# working.net
KiCad netlist of a schematic drawn in EAGLE
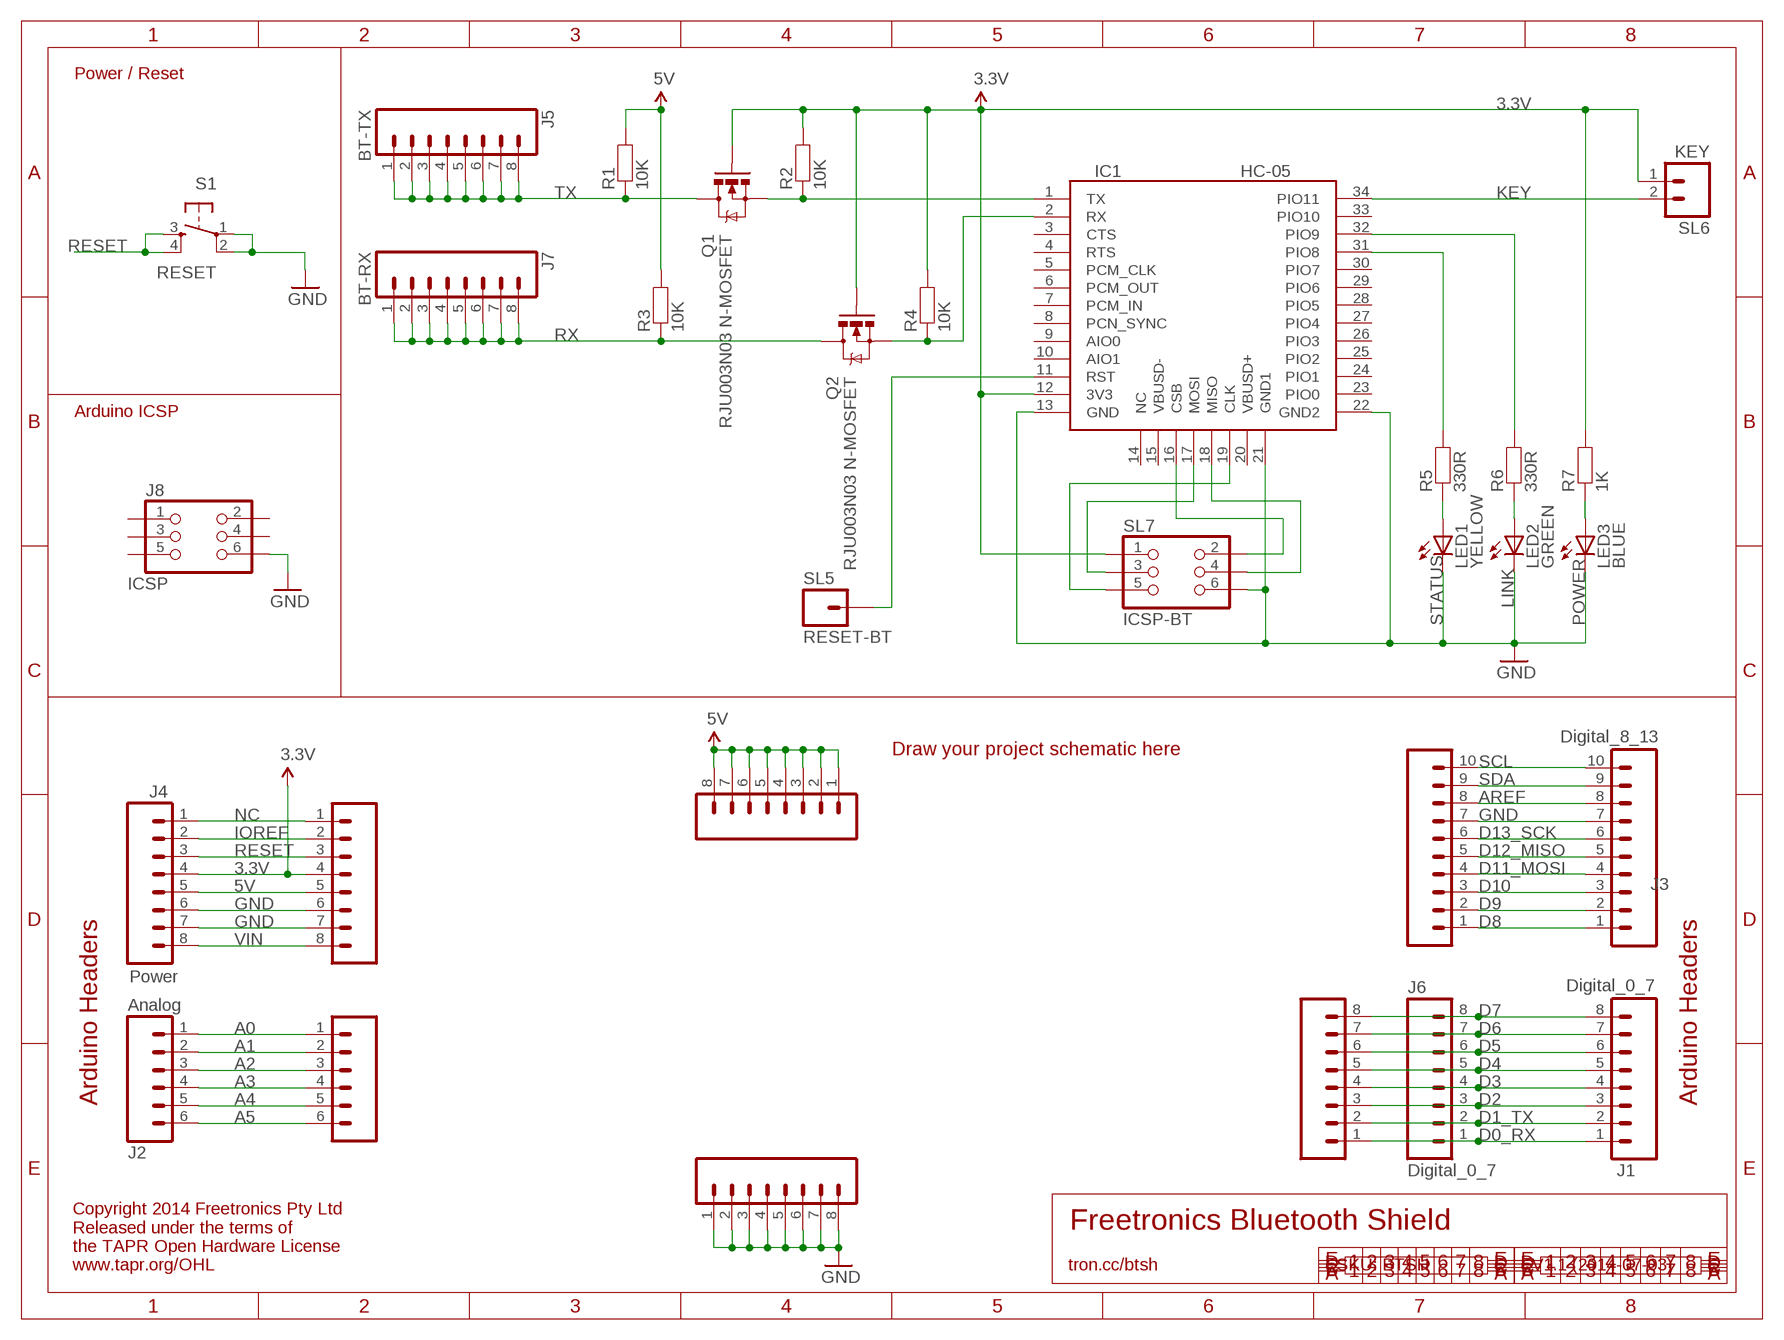
[diagram p0: schematic, sheet 1]

(export (version "E")
  (design (tool "Eeschema 10.0.6"))
  (components
    (comp (ref "IC1")
      (value "HC-05")
      (footprint "eagle-import:BLUETOOTH_SMD")
      (libsource (lib "eagle-import") (part "HC_05"))
    )
    (comp (ref "J1")
      (value "Digital_0_7")
      (footprint "eagle-import:1X08")
      (libsource (lib "eagle-import") (part "M08"))
    )
    (comp (ref "J2")
      (value "Analog")
      (footprint "eagle-import:1X06")
      (libsource (lib "eagle-import") (part "M06SIP"))
    )
    (comp (ref "J3")
      (value "Digital_8_13")
      (footprint "eagle-import:1X10")
      (libsource (lib "eagle-import") (part "M100.1"))
    )
    (comp (ref "J4")
      (value "Power")
      (footprint "eagle-import:1X08")
      (libsource (lib "eagle-import") (part "M08"))
    )
    (comp (ref "J5")
      (value "BT-TX")
      (footprint "eagle-import:1X08")
      (libsource (lib "eagle-import") (part "freetronics-original_M08"))
    )
    (comp (ref "J6")
      (value "Digital_0_7")
      (footprint "eagle-import:1X08")
      (libsource (lib "eagle-import") (part "freetronics-original_M08"))
    )
    (comp (ref "J7")
      (value "BT-RX")
      (footprint "eagle-import:1X08")
      (libsource (lib "eagle-import") (part "freetronics-original_M08"))
    )
    (comp (ref "J8")
      (value "ICSP")
      (footprint "eagle-import:2X03PTH")
      (libsource (lib "eagle-import") (part "ICSPPTH"))
    )
    (comp (ref "LED1")
      (value "YELLOW")
      (footprint "eagle-import:LED-0603")
      (libsource (lib "eagle-import") (part "LED0603"))
    )
    (comp (ref "LED2")
      (value "GREEN")
      (footprint "eagle-import:LED-0603")
      (libsource (lib "eagle-import") (part "LED0603"))
    )
    (comp (ref "LED3")
      (value "BLUE")
      (footprint "eagle-import:LED-0603")
      (libsource (lib "eagle-import") (part "LED0603"))
    )
    (comp (ref "Q1")
      (value "RJU003N03 N-MOSFET")
      (footprint "eagle-import:SOT32-3")
      (libsource (lib "eagle-import") (part "MOSFET-NSOT-323"))
    )
    (comp (ref "Q2")
      (value "RJU003N03 N-MOSFET")
      (footprint "eagle-import:SOT32-3")
      (libsource (lib "eagle-import") (part "MOSFET-NSOT-323"))
    )
    (comp (ref "R1")
      (value "10K")
      (footprint "eagle-import:0603")
      (libsource (lib "eagle-import") (part "RESISTOR0603"))
    )
    (comp (ref "R2")
      (value "10K")
      (footprint "eagle-import:0603")
      (libsource (lib "eagle-import") (part "RESISTOR0603"))
    )
    (comp (ref "R3")
      (value "10K")
      (footprint "eagle-import:0603")
      (libsource (lib "eagle-import") (part "RESISTOR0603"))
    )
    (comp (ref "R4")
      (value "10K")
      (footprint "eagle-import:0603")
      (libsource (lib "eagle-import") (part "RESISTOR0603"))
    )
    (comp (ref "R5")
      (value "330R")
      (footprint "eagle-import:0603")
      (libsource (lib "eagle-import") (part "RESISTOR0603"))
    )
    (comp (ref "R6")
      (value "330R")
      (footprint "eagle-import:0603")
      (libsource (lib "eagle-import") (part "RESISTOR0603"))
    )
    (comp (ref "R7")
      (value "1K")
      (footprint "eagle-import:0603")
      (libsource (lib "eagle-import") (part "RESISTOR0603"))
    )
    (comp (ref "S1")
      (value "RESET")
      (footprint "eagle-import:TACTILE_SWITCH_SMD")
      (libsource (lib "eagle-import") (part "TAC_SWITCHSMD"))
    )
    (comp (ref "SL1")
      (value "Digital_0_7")
      (footprint "eagle-import:1X08")
      (libsource (lib "eagle-import") (part "M08"))
    )
    (comp (ref "SL2")
      (value "Analog")
      (footprint "eagle-import:1X06")
      (libsource (lib "eagle-import") (part "M06SIP"))
    )
    (comp (ref "SL3")
      (value "Digital_8_13")
      (footprint "eagle-import:1X10")
      (libsource (lib "eagle-import") (part "M100.1"))
    )
    (comp (ref "SL4")
      (value "Power")
      (footprint "eagle-import:1X08")
      (libsource (lib "eagle-import") (part "M08"))
    )
    (comp (ref "SL5")
      (value "RESET-BT")
      (footprint "eagle-import:1X01")
      (libsource (lib "eagle-import") (part "M01PTH"))
    )
    (comp (ref "SL6")
      (value "KEY")
      (footprint "eagle-import:1X02")
      (libsource (lib "eagle-import") (part "M02PTH"))
    )
    (comp (ref "SL7")
      (value "ICSP-BT")
      (footprint "eagle-import:2X03PTH")
      (libsource (lib "eagle-import") (part "ICSPPTH"))
    )
    (comp (ref "SL8")
      (value "5V")
      (footprint "eagle-import:1X08")
      (libsource (lib "eagle-import") (part "M08"))
    )
    (comp (ref "SL9")
      (value "GND")
      (footprint "eagle-import:1X08")
      (libsource (lib "eagle-import") (part "M08"))
    )
  )
  (nets
    (net (code "1") (name "/A0") (class "Default")
      (node (ref "J2") (pin "1") (pinfunction "1_1") (pintype "passive"))
      (node (ref "SL2") (pin "1") (pinfunction "1_1") (pintype "passive"))
    )
    (net (code "2") (name "/A1") (class "Default")
      (node (ref "J2") (pin "2") (pinfunction "2_2") (pintype "passive"))
      (node (ref "SL2") (pin "2") (pinfunction "2_2") (pintype "passive"))
    )
    (net (code "3") (name "/A2") (class "Default")
      (node (ref "J2") (pin "3") (pinfunction "3_3") (pintype "passive"))
      (node (ref "SL2") (pin "3") (pinfunction "3_3") (pintype "passive"))
    )
    (net (code "4") (name "/A3") (class "Default")
      (node (ref "J2") (pin "4") (pinfunction "4_4") (pintype "passive"))
      (node (ref "SL2") (pin "4") (pinfunction "4_4") (pintype "passive"))
    )
    (net (code "5") (name "/A4") (class "Default")
      (node (ref "J2") (pin "5") (pinfunction "5_5") (pintype "passive"))
      (node (ref "SL2") (pin "5") (pinfunction "5_5") (pintype "passive"))
    )
    (net (code "6") (name "/A5") (class "Default")
      (node (ref "J2") (pin "6") (pinfunction "6_6") (pintype "passive"))
      (node (ref "SL2") (pin "6") (pinfunction "6_6") (pintype "passive"))
    )
    (net (code "7") (name "/AREF") (class "Default")
      (node (ref "J3") (pin "8") (pinfunction "8_8") (pintype "passive"))
      (node (ref "SL3") (pin "8") (pinfunction "8_8") (pintype "passive"))
    )
    (net (code "8") (name "/D0_RX") (class "Default")
      (node (ref "J1") (pin "1") (pinfunction "1_1") (pintype "passive"))
      (node (ref "J6") (pin "1") (pinfunction "1_1") (pintype "passive"))
      (node (ref "SL1") (pin "1") (pinfunction "1_1") (pintype "passive"))
    )
    (net (code "9") (name "/D1_TX") (class "Default")
      (node (ref "J1") (pin "2") (pinfunction "2_2") (pintype "passive"))
      (node (ref "J6") (pin "2") (pinfunction "2_2") (pintype "passive"))
      (node (ref "SL1") (pin "2") (pinfunction "2_2") (pintype "passive"))
    )
    (net (code "10") (name "/D2") (class "Default")
      (node (ref "J1") (pin "3") (pinfunction "3_3") (pintype "passive"))
      (node (ref "J6") (pin "3") (pinfunction "3_3") (pintype "passive"))
      (node (ref "SL1") (pin "3") (pinfunction "3_3") (pintype "passive"))
    )
    (net (code "11") (name "/D3") (class "Default")
      (node (ref "J1") (pin "4") (pinfunction "4_4") (pintype "passive"))
      (node (ref "J6") (pin "4") (pinfunction "4_4") (pintype "passive"))
      (node (ref "SL1") (pin "4") (pinfunction "4_4") (pintype "passive"))
    )
    (net (code "12") (name "/D4") (class "Default")
      (node (ref "J1") (pin "5") (pinfunction "5_5") (pintype "passive"))
      (node (ref "J6") (pin "5") (pinfunction "5_5") (pintype "passive"))
      (node (ref "SL1") (pin "5") (pinfunction "5_5") (pintype "passive"))
    )
    (net (code "13") (name "/D5") (class "Default")
      (node (ref "J1") (pin "6") (pinfunction "6_6") (pintype "passive"))
      (node (ref "J6") (pin "6") (pinfunction "6_6") (pintype "passive"))
      (node (ref "SL1") (pin "6") (pinfunction "6_6") (pintype "passive"))
    )
    (net (code "14") (name "/D6") (class "Default")
      (node (ref "J1") (pin "7") (pinfunction "7_7") (pintype "passive"))
      (node (ref "J6") (pin "7") (pinfunction "7_7") (pintype "passive"))
      (node (ref "SL1") (pin "7") (pinfunction "7_7") (pintype "passive"))
    )
    (net (code "15") (name "/D7") (class "Default")
      (node (ref "J1") (pin "8") (pinfunction "8_8") (pintype "passive"))
      (node (ref "J6") (pin "8") (pinfunction "8_8") (pintype "passive"))
      (node (ref "SL1") (pin "8") (pinfunction "8_8") (pintype "passive"))
    )
    (net (code "16") (name "/D8") (class "Default")
      (node (ref "J3") (pin "1") (pinfunction "1_1") (pintype "passive"))
      (node (ref "SL3") (pin "1") (pinfunction "1_1") (pintype "passive"))
    )
    (net (code "17") (name "/D9") (class "Default")
      (node (ref "J3") (pin "2") (pinfunction "2_2") (pintype "passive"))
      (node (ref "SL3") (pin "2") (pinfunction "2_2") (pintype "passive"))
    )
    (net (code "18") (name "/D10") (class "Default")
      (node (ref "J3") (pin "3") (pinfunction "3_3") (pintype "passive"))
      (node (ref "SL3") (pin "3") (pinfunction "3_3") (pintype "passive"))
    )
    (net (code "19") (name "/D11_MOSI") (class "Default")
      (node (ref "J3") (pin "4") (pinfunction "4_4") (pintype "passive"))
      (node (ref "SL3") (pin "4") (pinfunction "4_4") (pintype "passive"))
    )
    (net (code "20") (name "/D12_MISO") (class "Default")
      (node (ref "J3") (pin "5") (pinfunction "5_5") (pintype "passive"))
      (node (ref "SL3") (pin "5") (pinfunction "5_5") (pintype "passive"))
    )
    (net (code "21") (name "/D13_SCK") (class "Default")
      (node (ref "J3") (pin "6") (pinfunction "6_6") (pintype "passive"))
      (node (ref "SL3") (pin "6") (pinfunction "6_6") (pintype "passive"))
    )
    (net (code "22") (name "/IOREF") (class "Default")
      (node (ref "J4") (pin "2") (pinfunction "2_2") (pintype "passive"))
      (node (ref "SL4") (pin "2") (pinfunction "2_2") (pintype "passive"))
    )
    (net (code "23") (name "/KEY") (class "Default")
      (node (ref "IC1") (pin "34") (pinfunction "PIO11_34") (pintype "bidirectional"))
      (node (ref "SL6") (pin "2") (pinfunction "2_2") (pintype "passive"))
    )
    (net (code "24") (name "/NC") (class "Default")
      (node (ref "J4") (pin "1") (pinfunction "1_1") (pintype "passive"))
      (node (ref "SL4") (pin "1") (pinfunction "1_1") (pintype "passive"))
    )
    (net (code "25") (name "/RESET") (class "Default")
      (node (ref "J4") (pin "3") (pinfunction "3_3") (pintype "passive"))
      (node (ref "S1") (pin "3") (pinfunction "3_3") (pintype "passive"))
      (node (ref "S1") (pin "4") (pinfunction "4_4") (pintype "passive"))
      (node (ref "SL4") (pin "3") (pinfunction "3_3") (pintype "passive"))
    )
    (net (code "26") (name "/RX") (class "Default")
      (node (ref "J7") (pin "1") (pinfunction "1_1") (pintype "passive"))
      (node (ref "J7") (pin "2") (pinfunction "2_2") (pintype "passive"))
      (node (ref "J7") (pin "3") (pinfunction "3_3") (pintype "passive"))
      (node (ref "J7") (pin "4") (pinfunction "4_4") (pintype "passive"))
      (node (ref "J7") (pin "5") (pinfunction "5_5") (pintype "passive"))
      (node (ref "J7") (pin "6") (pinfunction "6_6") (pintype "passive"))
      (node (ref "J7") (pin "7") (pinfunction "7_7") (pintype "passive"))
      (node (ref "J7") (pin "8") (pinfunction "8_8") (pintype "passive"))
      (node (ref "Q2") (pin "3") (pinfunction "D_3") (pintype "passive"))
      (node (ref "R3") (pin "1") (pinfunction "1_1") (pintype "passive"))
    )
    (net (code "27") (name "/SCL") (class "Default")
      (node (ref "J3") (pin "10") (pinfunction "10_10") (pintype "passive"))
      (node (ref "SL3") (pin "10") (pinfunction "10_10") (pintype "passive"))
    )
    (net (code "28") (name "/SDA") (class "Default")
      (node (ref "J3") (pin "9") (pinfunction "9_9") (pintype "passive"))
      (node (ref "SL3") (pin "9") (pinfunction "9_9") (pintype "passive"))
    )
    (net (code "29") (name "/TX") (class "Default")
      (node (ref "J5") (pin "1") (pinfunction "1_1") (pintype "passive"))
      (node (ref "J5") (pin "2") (pinfunction "2_2") (pintype "passive"))
      (node (ref "J5") (pin "3") (pinfunction "3_3") (pintype "passive"))
      (node (ref "J5") (pin "4") (pinfunction "4_4") (pintype "passive"))
      (node (ref "J5") (pin "5") (pinfunction "5_5") (pintype "passive"))
      (node (ref "J5") (pin "6") (pinfunction "6_6") (pintype "passive"))
      (node (ref "J5") (pin "7") (pinfunction "7_7") (pintype "passive"))
      (node (ref "J5") (pin "8") (pinfunction "8_8") (pintype "passive"))
      (node (ref "Q1") (pin "3") (pinfunction "D_3") (pintype "passive"))
      (node (ref "R1") (pin "1") (pinfunction "1_1") (pintype "passive"))
    )
    (net (code "30") (name "/VIN") (class "Default")
      (node (ref "J4") (pin "8") (pinfunction "8_8") (pintype "passive"))
      (node (ref "SL4") (pin "8") (pinfunction "8_8") (pintype "passive"))
    )
    (net (code "31") (name "3.3V") (class "Default")
      (node (ref "IC1") (pin "12") (pinfunction "3V3_12") (pintype "bidirectional"))
      (node (ref "J4") (pin "4") (pinfunction "4_4") (pintype "passive"))
      (node (ref "Q1") (pin "1") (pinfunction "G_1") (pintype "passive"))
      (node (ref "Q2") (pin "1") (pinfunction "G_1") (pintype "passive"))
      (node (ref "R2") (pin "2") (pinfunction "2_2") (pintype "passive"))
      (node (ref "R4") (pin "2") (pinfunction "2_2") (pintype "passive"))
      (node (ref "R7") (pin "2") (pinfunction "2_2") (pintype "passive"))
      (node (ref "SL4") (pin "4") (pinfunction "4_4") (pintype "passive"))
      (node (ref "SL6") (pin "1") (pinfunction "1_1") (pintype "passive"))
      (node (ref "SL7") (pin "1") (pinfunction "1_1") (pintype "passive"))
    )
    (net (code "32") (name "5V") (class "Default")
      (node (ref "J4") (pin "5") (pinfunction "5_5") (pintype "passive"))
      (node (ref "R1") (pin "2") (pinfunction "2_2") (pintype "passive"))
      (node (ref "R3") (pin "2") (pinfunction "2_2") (pintype "passive"))
      (node (ref "SL4") (pin "5") (pinfunction "5_5") (pintype "passive"))
      (node (ref "SL8") (pin "1") (pinfunction "1_1") (pintype "passive"))
      (node (ref "SL8") (pin "2") (pinfunction "2_2") (pintype "passive"))
      (node (ref "SL8") (pin "3") (pinfunction "3_3") (pintype "passive"))
      (node (ref "SL8") (pin "4") (pinfunction "4_4") (pintype "passive"))
      (node (ref "SL8") (pin "5") (pinfunction "5_5") (pintype "passive"))
      (node (ref "SL8") (pin "6") (pinfunction "6_6") (pintype "passive"))
      (node (ref "SL8") (pin "7") (pinfunction "7_7") (pintype "passive"))
      (node (ref "SL8") (pin "8") (pinfunction "8_8") (pintype "passive"))
    )
    (net (code "33") (name "GND") (class "Default")
      (node (ref "IC1") (pin "13") (pinfunction "GND_13") (pintype "bidirectional"))
      (node (ref "IC1") (pin "21") (pinfunction "GND1_21") (pintype "bidirectional"))
      (node (ref "IC1") (pin "22") (pinfunction "GND2_22") (pintype "bidirectional"))
      (node (ref "J3") (pin "7") (pinfunction "7_7") (pintype "passive"))
      (node (ref "J4") (pin "6") (pinfunction "6_6") (pintype "passive"))
      (node (ref "J4") (pin "7") (pinfunction "7_7") (pintype "passive"))
      (node (ref "J8") (pin "6") (pinfunction "6_6") (pintype "passive"))
      (node (ref "LED1") (pin "C") (pinfunction "C_C") (pintype "passive"))
      (node (ref "LED2") (pin "C") (pinfunction "C_C") (pintype "passive"))
      (node (ref "LED3") (pin "C") (pinfunction "C_C") (pintype "passive"))
      (node (ref "S1") (pin "1") (pinfunction "1_1") (pintype "passive"))
      (node (ref "S1") (pin "2") (pinfunction "2_2") (pintype "passive"))
      (node (ref "SL3") (pin "7") (pinfunction "7_7") (pintype "passive"))
      (node (ref "SL4") (pin "6") (pinfunction "6_6") (pintype "passive"))
      (node (ref "SL4") (pin "7") (pinfunction "7_7") (pintype "passive"))
      (node (ref "SL7") (pin "6") (pinfunction "6_6") (pintype "passive"))
      (node (ref "SL9") (pin "1") (pinfunction "1_1") (pintype "passive"))
      (node (ref "SL9") (pin "2") (pinfunction "2_2") (pintype "passive"))
      (node (ref "SL9") (pin "3") (pinfunction "3_3") (pintype "passive"))
      (node (ref "SL9") (pin "4") (pinfunction "4_4") (pintype "passive"))
      (node (ref "SL9") (pin "5") (pinfunction "5_5") (pintype "passive"))
      (node (ref "SL9") (pin "6") (pinfunction "6_6") (pintype "passive"))
      (node (ref "SL9") (pin "7") (pinfunction "7_7") (pintype "passive"))
      (node (ref "SL9") (pin "8") (pinfunction "8_8") (pintype "passive"))
    )
    (net (code "34") (name "Net-(IC1-CLK)") (class "Default")
      (node (ref "IC1") (pin "19") (pinfunction "CLK_19") (pintype "bidirectional"))
      (node (ref "SL7") (pin "5") (pinfunction "5_5") (pintype "passive"))
    )
    (net (code "35") (name "Net-(IC1-CSB)") (class "Default")
      (node (ref "IC1") (pin "16") (pinfunction "CSB_16") (pintype "bidirectional"))
      (node (ref "SL7") (pin "2") (pinfunction "2_2") (pintype "passive"))
    )
    (net (code "36") (name "Net-(IC1-MISO)") (class "Default")
      (node (ref "IC1") (pin "18") (pinfunction "MISO_18") (pintype "bidirectional"))
      (node (ref "SL7") (pin "4") (pinfunction "4_4") (pintype "passive"))
    )
    (net (code "37") (name "Net-(IC1-MOSI)") (class "Default")
      (node (ref "IC1") (pin "17") (pinfunction "MOSI_17") (pintype "bidirectional"))
      (node (ref "SL7") (pin "3") (pinfunction "3_3") (pintype "passive"))
    )
    (net (code "38") (name "Net-(IC1-PIO8)") (class "Default")
      (node (ref "IC1") (pin "31") (pinfunction "PIO8_31") (pintype "bidirectional"))
      (node (ref "R5") (pin "2") (pinfunction "2_2") (pintype "passive"))
    )
    (net (code "39") (name "Net-(IC1-PIO9)") (class "Default")
      (node (ref "IC1") (pin "32") (pinfunction "PIO9_32") (pintype "bidirectional"))
      (node (ref "R6") (pin "2") (pinfunction "2_2") (pintype "passive"))
    )
    (net (code "40") (name "Net-(IC1-RST)") (class "Default")
      (node (ref "IC1") (pin "11") (pinfunction "RST_11") (pintype "bidirectional"))
      (node (ref "SL5") (pin "1") (pinfunction "1_1") (pintype "passive"))
    )
    (net (code "41") (name "Net-(IC1-RX)") (class "Default")
      (node (ref "IC1") (pin "2") (pinfunction "RX_2") (pintype "bidirectional"))
      (node (ref "Q2") (pin "2") (pinfunction "S_2") (pintype "passive"))
      (node (ref "R4") (pin "1") (pinfunction "1_1") (pintype "passive"))
    )
    (net (code "42") (name "Net-(IC1-TX)") (class "Default")
      (node (ref "IC1") (pin "1") (pinfunction "TX_1") (pintype "bidirectional"))
      (node (ref "Q1") (pin "2") (pinfunction "S_2") (pintype "passive"))
      (node (ref "R2") (pin "1") (pinfunction "1_1") (pintype "passive"))
    )
    (net (code "43") (name "Net-(LED1-PadA)") (class "Default")
      (node (ref "LED1") (pin "A") (pinfunction "A_A") (pintype "passive"))
      (node (ref "R5") (pin "1") (pinfunction "1_1") (pintype "passive"))
    )
    (net (code "44") (name "Net-(LED2-PadA)") (class "Default")
      (node (ref "LED2") (pin "A") (pinfunction "A_A") (pintype "passive"))
      (node (ref "R6") (pin "1") (pinfunction "1_1") (pintype "passive"))
    )
    (net (code "45") (name "Net-(LED3-PadA)") (class "Default")
      (node (ref "LED3") (pin "A") (pinfunction "A_A") (pintype "passive"))
      (node (ref "R7") (pin "1") (pinfunction "1_1") (pintype "passive"))
    )
    (net (code "46") (name "unconnected-(IC1-AIO0-Pad9)") (class "Default")
      (node (ref "IC1") (pin "9") (pinfunction "AIO0_9") (pintype "bidirectional"))
    )
    (net (code "47") (name "unconnected-(IC1-AIO1-Pad10)") (class "Default")
      (node (ref "IC1") (pin "10") (pinfunction "AIO1_10") (pintype "bidirectional"))
    )
    (net (code "48") (name "unconnected-(IC1-CTS-Pad3)") (class "Default")
      (node (ref "IC1") (pin "3") (pinfunction "CTS_3") (pintype "bidirectional"))
    )
    (net (code "49") (name "unconnected-(IC1-NC-Pad14)") (class "Default")
      (node (ref "IC1") (pin "14") (pinfunction "NC_14") (pintype "bidirectional"))
    )
    (net (code "50") (name "unconnected-(IC1-PCM_CLK-Pad5)") (class "Default")
      (node (ref "IC1") (pin "5") (pinfunction "PCM_CLK_5") (pintype "bidirectional"))
    )
    (net (code "51") (name "unconnected-(IC1-PCM_IN-Pad7)") (class "Default")
      (node (ref "IC1") (pin "7") (pinfunction "PCM_IN_7") (pintype "bidirectional"))
    )
    (net (code "52") (name "unconnected-(IC1-PCM_OUT-Pad6)") (class "Default")
      (node (ref "IC1") (pin "6") (pinfunction "PCM_OUT_6") (pintype "bidirectional"))
    )
    (net (code "53") (name "unconnected-(IC1-PCN_SYNC-Pad8)") (class "Default")
      (node (ref "IC1") (pin "8") (pinfunction "PCN_SYNC_8") (pintype "bidirectional"))
    )
    (net (code "54") (name "unconnected-(IC1-PIO0-Pad23)") (class "Default")
      (node (ref "IC1") (pin "23") (pinfunction "PIO0_23") (pintype "bidirectional"))
    )
    (net (code "55") (name "unconnected-(IC1-PIO1-Pad24)") (class "Default")
      (node (ref "IC1") (pin "24") (pinfunction "PIO1_24") (pintype "bidirectional"))
    )
    (net (code "56") (name "unconnected-(IC1-PIO2-Pad25)") (class "Default")
      (node (ref "IC1") (pin "25") (pinfunction "PIO2_25") (pintype "bidirectional"))
    )
    (net (code "57") (name "unconnected-(IC1-PIO3-Pad26)") (class "Default")
      (node (ref "IC1") (pin "26") (pinfunction "PIO3_26") (pintype "bidirectional"))
    )
    (net (code "58") (name "unconnected-(IC1-PIO4-Pad27)") (class "Default")
      (node (ref "IC1") (pin "27") (pinfunction "PIO4_27") (pintype "bidirectional"))
    )
    (net (code "59") (name "unconnected-(IC1-PIO5-Pad28)") (class "Default")
      (node (ref "IC1") (pin "28") (pinfunction "PIO5_28") (pintype "bidirectional"))
    )
    (net (code "60") (name "unconnected-(IC1-PIO6-Pad29)") (class "Default")
      (node (ref "IC1") (pin "29") (pinfunction "PIO6_29") (pintype "bidirectional"))
    )
    (net (code "61") (name "unconnected-(IC1-PIO7-Pad30)") (class "Default")
      (node (ref "IC1") (pin "30") (pinfunction "PIO7_30") (pintype "bidirectional"))
    )
    (net (code "62") (name "unconnected-(IC1-PIO10-Pad33)") (class "Default")
      (node (ref "IC1") (pin "33") (pinfunction "PIO10_33") (pintype "bidirectional"))
    )
    (net (code "63") (name "unconnected-(IC1-RTS-Pad4)") (class "Default")
      (node (ref "IC1") (pin "4") (pinfunction "RTS_4") (pintype "bidirectional"))
    )
    (net (code "64") (name "unconnected-(IC1-VBUSD+-Pad20)") (class "Default")
      (node (ref "IC1") (pin "20") (pinfunction "VBUSD+_20") (pintype "bidirectional"))
    )
    (net (code "65") (name "unconnected-(IC1-VBUSD--Pad15)") (class "Default")
      (node (ref "IC1") (pin "15") (pinfunction "VBUSD-_15") (pintype "bidirectional"))
    )
    (net (code "66") (name "unconnected-(J8-Pad1)") (class "Default")
      (node (ref "J8") (pin "1") (pinfunction "1_1") (pintype "passive"))
    )
    (net (code "67") (name "unconnected-(J8-Pad2)") (class "Default")
      (node (ref "J8") (pin "2") (pinfunction "2_2") (pintype "passive"))
    )
    (net (code "68") (name "unconnected-(J8-Pad3)") (class "Default")
      (node (ref "J8") (pin "3") (pinfunction "3_3") (pintype "passive"))
    )
    (net (code "69") (name "unconnected-(J8-Pad4)") (class "Default")
      (node (ref "J8") (pin "4") (pinfunction "4_4") (pintype "passive"))
    )
    (net (code "70") (name "unconnected-(J8-Pad5)") (class "Default")
      (node (ref "J8") (pin "5") (pinfunction "5_5") (pintype "passive"))
    )
  )
)
